# Schematic.net
KiCad netlist of a schematic drawn in Altium Designer
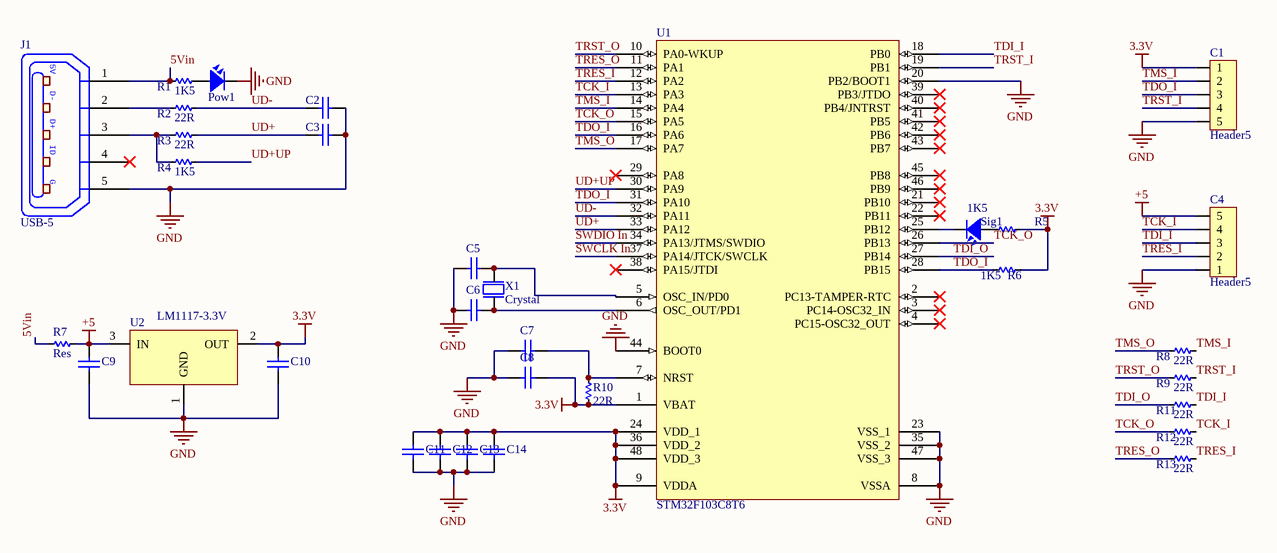
[diagram p0: Schematic.SchDoc]

(export (version "E")
  (design (tool "Eeschema 10.0.6"))
  (components
    (comp (ref "C1")
      (value "Header5")
      (footprint "Header5 SMD")
      (description "Header IDC, 5 x 1 Pin Vertical 2.54mm Pitch (Non-Boxed, Male)")
      (fields
        (field (name "MANUFACTURER") "Würth Elektronik eiSos GmbH")
        (field (name "PARTNO") "613002143121")
        (field (name "CREATED BY") "Karrer Zheng")
      )
      (libsource (lib "MQCrexcelV1.0") (part "Header5"))
    )
    (comp (ref "C2")
      (value "Capacitor Ceramic")
      (footprint "C0805")
      (description "Capacitor")
      (fields (field (name "PUBLISHER") "Altium Limited"))
      (libsource (lib "NBBLib 14-03-2012") (part "CapSMD"))
    )
    (comp (ref "C3")
      (value "Capacitor Ceramic")
      (footprint "C0805")
      (description "Capacitor")
      (fields (field (name "PUBLISHER") "Altium Limited"))
      (libsource (lib "NBBLib 14-03-2012") (part "CapSMD"))
    )
    (comp (ref "C4")
      (value "Header5")
      (footprint "Header5 SMD")
      (description "Header IDC, 5 x 1 Pin Vertical 2.54mm Pitch (Non-Boxed, Male)")
      (fields
        (field (name "MANUFACTURER") "Würth Elektronik eiSos GmbH")
        (field (name "PARTNO") "613002143121")
        (field (name "CREATED BY") "Karrer Zheng")
      )
      (libsource (lib "") (part "Header5_1"))
    )
    (comp (ref "C5")
      (value "Capacitor Ceramic")
      (footprint "C0805")
      (description "Capacitor")
      (fields (field (name "PUBLISHER") "Altium Limited"))
      (libsource (lib "NBBLib 14-03-2012") (part "CapSMD"))
    )
    (comp (ref "C6")
      (value "Capacitor Ceramic")
      (footprint "C0805")
      (description "Capacitor")
      (fields (field (name "PUBLISHER") "Altium Limited"))
      (libsource (lib "NBBLib 14-03-2012") (part "CapSMD"))
    )
    (comp (ref "C7")
      (value "Capacitor Ceramic")
      (footprint "C0805")
      (description "Capacitor")
      (fields (field (name "PUBLISHER") "Altium Limited"))
      (libsource (lib "NBBLib 14-03-2012") (part "CapSMD"))
    )
    (comp (ref "C8")
      (value "Capacitor Ceramic")
      (footprint "C0805")
      (description "Capacitor")
      (fields (field (name "PUBLISHER") "Altium Limited"))
      (libsource (lib "NBBLib 14-03-2012") (part "CapSMD"))
    )
    (comp (ref "C9")
      (value "Capacitor Ceramic")
      (footprint "C0805")
      (description "Capacitor")
      (fields (field (name "PUBLISHER") "Altium Limited"))
      (libsource (lib "NBBLib 14-03-2012") (part "CapSMD"))
    )
    (comp (ref "C10")
      (value "Capacitor Ceramic")
      (footprint "C0805")
      (description "Capacitor")
      (fields (field (name "PUBLISHER") "Altium Limited"))
      (libsource (lib "NBBLib 14-03-2012") (part "CapSMD"))
    )
    (comp (ref "C11")
      (value "Capacitor Ceramic")
      (footprint "C0805")
      (description "Capacitor")
      (fields (field (name "PUBLISHER") "Altium Limited"))
      (libsource (lib "NBBLib 14-03-2012") (part "CapSMD"))
    )
    (comp (ref "C12")
      (value "Capacitor Ceramic")
      (footprint "C0805")
      (description "Capacitor")
      (fields (field (name "PUBLISHER") "Altium Limited"))
      (libsource (lib "NBBLib 14-03-2012") (part "CapSMD"))
    )
    (comp (ref "C13")
      (value "Capacitor Ceramic")
      (footprint "C0805")
      (description "Capacitor")
      (fields (field (name "PUBLISHER") "Altium Limited"))
      (libsource (lib "NBBLib 14-03-2012") (part "CapSMD"))
    )
    (comp (ref "C14")
      (value "Capacitor Ceramic")
      (footprint "C0805")
      (description "Capacitor")
      (fields (field (name "PUBLISHER") "Altium Limited"))
      (libsource (lib "NBBLib 14-03-2012") (part "CapSMD"))
    )
    (comp (ref "J1")
      (value "USB-5")
      (footprint "USB-M1")
      (fields
        (field (name "MANUFACTURER") "FCI")
        (field (name "MANUFACTURER PART NUMBER") "10118193-0001LF")
        (field (name ".CREATOR") "MM")
        (field (name ".CHECKED PCB") "RF")
        (field (name ".CHECKED SCH") "MM")
      )
      (libsource (lib "MQCrexcelV1.0") (part "USB-5"))
    )
    (comp (ref "Pow1")
      (value "LED")
      (footprint "LED-0805-Red")
      (libsource (lib "MQCrexcelV1.0") (part "LED SMD"))
    )
    (comp (ref "R1")
      (value "1K5")
      (footprint "RES-SMD-0603")
      (description "Resistor")
      (fields
        (field (name "MANUFACTURER") "Generic Components")
        (field (name "PUBLISHER") "Altium Hobart Technology Centre")
      )
      (libsource (lib "MQCrexcelV1.0") (part "Res-SMD"))
    )
    (comp (ref "R2")
      (value "22R")
      (footprint "RES-SMD-0603")
      (description "Resistor")
      (fields
        (field (name "MANUFACTURER") "Generic Components")
        (field (name "PUBLISHER") "Altium Hobart Technology Centre")
      )
      (libsource (lib "MQCrexcelV1.0") (part "Res-SMD"))
    )
    (comp (ref "R3")
      (value "22R")
      (footprint "RES-SMD-0603")
      (description "Resistor")
      (fields
        (field (name "MANUFACTURER") "Generic Components")
        (field (name "PUBLISHER") "Altium Hobart Technology Centre")
      )
      (libsource (lib "MQCrexcelV1.0") (part "Res-SMD"))
    )
    (comp (ref "R4")
      (value "1K5")
      (footprint "RES-SMD-0603")
      (description "Resistor")
      (fields
        (field (name "MANUFACTURER") "Generic Components")
        (field (name "PUBLISHER") "Altium Hobart Technology Centre")
      )
      (libsource (lib "MQCrexcelV1.0") (part "Res-SMD"))
    )
    (comp (ref "R5")
      (value "1K5")
      (footprint "RES-SMD-0603")
      (description "Resistor")
      (fields
        (field (name "MANUFACTURER") "Generic Components")
        (field (name "PUBLISHER") "Altium Hobart Technology Centre")
      )
      (libsource (lib "MQCrexcelV1.0") (part "Res-SMD"))
    )
    (comp (ref "R6")
      (value "1K5")
      (footprint "RES-SMD-0603")
      (description "Resistor")
      (fields
        (field (name "MANUFACTURER") "Generic Components")
        (field (name "PUBLISHER") "Altium Hobart Technology Centre")
      )
      (libsource (lib "MQCrexcelV1.0") (part "Res-SMD"))
    )
    (comp (ref "R7")
      (value "Res")
      (footprint "RES-SMD-1206")
      (description "Resistor")
      (fields
        (field (name "MANUFACTURER") "Generic Components")
        (field (name "PUBLISHER") "Altium Hobart Technology Centre")
      )
      (libsource (lib "MQCrexcelV1.0") (part "Res-SMD"))
    )
    (comp (ref "R8")
      (value "22R")
      (footprint "RES-SMD-0603")
      (description "Resistor")
      (fields
        (field (name "MANUFACTURER") "Generic Components")
        (field (name "PUBLISHER") "Altium Hobart Technology Centre")
      )
      (libsource (lib "MQCrexcelV1.0") (part "Res-SMD"))
    )
    (comp (ref "R9")
      (value "22R")
      (footprint "RES-SMD-0603")
      (description "Resistor")
      (fields
        (field (name "MANUFACTURER") "Generic Components")
        (field (name "PUBLISHER") "Altium Hobart Technology Centre")
      )
      (libsource (lib "MQCrexcelV1.0") (part "Res-SMD"))
    )
    (comp (ref "R10")
      (value "22R")
      (footprint "RES-SMD-0603")
      (description "Resistor")
      (fields
        (field (name "MANUFACTURER") "Generic Components")
        (field (name "PUBLISHER") "Altium Hobart Technology Centre")
      )
      (libsource (lib "MQCrexcelV1.0") (part "Res-SMD"))
    )
    (comp (ref "R11")
      (value "22R")
      (footprint "RES-SMD-0603")
      (description "Resistor")
      (fields
        (field (name "MANUFACTURER") "Generic Components")
        (field (name "PUBLISHER") "Altium Hobart Technology Centre")
      )
      (libsource (lib "MQCrexcelV1.0") (part "Res-SMD"))
    )
    (comp (ref "R12")
      (value "22R")
      (footprint "RES-SMD-0603")
      (description "Resistor")
      (fields
        (field (name "MANUFACTURER") "Generic Components")
        (field (name "PUBLISHER") "Altium Hobart Technology Centre")
      )
      (libsource (lib "MQCrexcelV1.0") (part "Res-SMD"))
    )
    (comp (ref "R13")
      (value "22R")
      (footprint "RES-SMD-0603")
      (description "Resistor")
      (fields
        (field (name "MANUFACTURER") "Generic Components")
        (field (name "PUBLISHER") "Altium Hobart Technology Centre")
      )
      (libsource (lib "MQCrexcelV1.0") (part "Res-SMD"))
    )
    (comp (ref "Sig1")
      (value "LED")
      (footprint "LED-0805-Red")
      (libsource (lib "MQCrexcelV1.0") (part "LED SMD"))
    )
    (comp (ref "U1")
      (value "STM32F103C8T6")
      (footprint "LQFP48_N")
      (description "STM32 ARM-based 32-bit MCU with 64 Kbytes Flash, 48-pin LQFP, Industrial Temperature")
      (fields (field (name "PUBLISHER") "Altium Limited"))
      (libsource (lib "ST Microcontroller 32-Bit STM32") (part "STM32F103C8T6"))
    )
    (comp (ref "U2")
      (value "LM1117-3.3V")
      (footprint "SOT223")
      (description "800mA Low-Dropout Linear Regulator")
      (fields (field (name "CREATOR") "Nguyen Ba Bien"))
      (libsource (lib "MQCrexcelV1.0") (part "LM1117"))
    )
    (comp (ref "X1")
      (value "Crystal")
      (footprint "Crystal")
      (libsource (lib "MQCrexcelV1.0") (part "Crystal"))
    )
  )
  (nets
    (net (code "1") (name "+5") (class "Default")
      (node (ref "C4") (pin "5") (pinfunction "5_5") (pintype "passive"))
      (node (ref "C9") (pin "1") (pinfunction "1_1") (pintype "passive"))
      (node (ref "R7") (pin "1") (pinfunction "1_1") (pintype "passive"))
      (node (ref "U2") (pin "3") (pinfunction "IN_3") (pintype "passive"))
    )
    (net (code "2") (name "/5Vin") (class "Default")
      (node (ref "J1") (pin "1") (pinfunction "P1_1") (pintype "passive"))
      (node (ref "R1") (pin "2") (pinfunction "2_2") (pintype "passive"))
      (node (ref "R7") (pin "2") (pinfunction "2_2") (pintype "passive"))
    )
    (net (code "3") (name "/SWCLK In") (class "Default")
      (node (ref "U1") (pin "37") (pinfunction "PA14/JTCK/SWCLK_37") (pintype "bidirectional"))
    )
    (net (code "4") (name "/SWDIO In") (class "Default")
      (node (ref "U1") (pin "34") (pinfunction "PA13/JTMS/SWDIO_34") (pintype "bidirectional"))
    )
    (net (code "5") (name "/TCK_I") (class "Default")
      (node (ref "C4") (pin "4") (pinfunction "4_4") (pintype "passive"))
      (node (ref "R12") (pin "1") (pinfunction "1_1") (pintype "passive"))
      (node (ref "U1") (pin "13") (pinfunction "PA3_13") (pintype "bidirectional"))
    )
    (net (code "6") (name "/TCK_O") (class "Default")
      (node (ref "R12") (pin "2") (pinfunction "2_2") (pintype "passive"))
      (node (ref "U1") (pin "15") (pinfunction "PA5_15") (pintype "bidirectional"))
      (node (ref "U1") (pin "26") (pinfunction "PB13_26") (pintype "bidirectional"))
    )
    (net (code "7") (name "/TDI_I") (class "Default")
      (node (ref "C4") (pin "3") (pinfunction "3_3") (pintype "passive"))
      (node (ref "R11") (pin "1") (pinfunction "1_1") (pintype "passive"))
      (node (ref "U1") (pin "18") (pinfunction "PB0_18") (pintype "bidirectional"))
    )
    (net (code "8") (name "/TDI_O") (class "Default")
      (node (ref "R11") (pin "2") (pinfunction "2_2") (pintype "passive"))
      (node (ref "U1") (pin "27") (pinfunction "PB14_27") (pintype "bidirectional"))
    )
    (net (code "9") (name "/TDO_I") (class "Default")
      (node (ref "C1") (pin "3") (pinfunction "3_3") (pintype "passive"))
      (node (ref "R6") (pin "1") (pinfunction "1_1") (pintype "passive"))
      (node (ref "U1") (pin "16") (pinfunction "PA6_16") (pintype "bidirectional"))
      (node (ref "U1") (pin "28") (pinfunction "PB15_28") (pintype "bidirectional"))
      (node (ref "U1") (pin "31") (pinfunction "PA10_31") (pintype "bidirectional"))
    )
    (net (code "10") (name "/TMS_I") (class "Default")
      (node (ref "C1") (pin "2") (pinfunction "2_2") (pintype "passive"))
      (node (ref "R8") (pin "1") (pinfunction "1_1") (pintype "passive"))
      (node (ref "U1") (pin "14") (pinfunction "PA4_14") (pintype "bidirectional"))
    )
    (net (code "11") (name "/TMS_O") (class "Default")
      (node (ref "R8") (pin "2") (pinfunction "2_2") (pintype "passive"))
      (node (ref "U1") (pin "17") (pinfunction "PA7_17") (pintype "bidirectional"))
    )
    (net (code "12") (name "/TRES_I") (class "Default")
      (node (ref "C4") (pin "2") (pinfunction "2_2") (pintype "passive"))
      (node (ref "R13") (pin "1") (pinfunction "1_1") (pintype "passive"))
      (node (ref "U1") (pin "12") (pinfunction "PA2_12") (pintype "bidirectional"))
    )
    (net (code "13") (name "/TRES_O") (class "Default")
      (node (ref "R13") (pin "2") (pinfunction "2_2") (pintype "passive"))
      (node (ref "U1") (pin "11") (pinfunction "PA1_11") (pintype "bidirectional"))
    )
    (net (code "14") (name "/TRST_I") (class "Default")
      (node (ref "C1") (pin "4") (pinfunction "4_4") (pintype "passive"))
      (node (ref "R9") (pin "1") (pinfunction "1_1") (pintype "passive"))
      (node (ref "U1") (pin "19") (pinfunction "PB1_19") (pintype "bidirectional"))
    )
    (net (code "15") (name "/TRST_O") (class "Default")
      (node (ref "R9") (pin "2") (pinfunction "2_2") (pintype "passive"))
      (node (ref "U1") (pin "10") (pinfunction "PA0-WKUP_10") (pintype "bidirectional"))
    )
    (net (code "16") (name "/UD+") (class "Default")
      (node (ref "C3") (pin "2") (pinfunction "2_2") (pintype "passive"))
      (node (ref "R3") (pin "1") (pinfunction "1_1") (pintype "passive"))
      (node (ref "U1") (pin "33") (pinfunction "PA12_33") (pintype "bidirectional"))
    )
    (net (code "17") (name "/UD+UP") (class "Default")
      (node (ref "R4") (pin "1") (pinfunction "1_1") (pintype "passive"))
      (node (ref "U1") (pin "30") (pinfunction "PA9_30") (pintype "bidirectional"))
    )
    (net (code "18") (name "/UD-") (class "Default")
      (node (ref "C2") (pin "2") (pinfunction "2_2") (pintype "passive"))
      (node (ref "R2") (pin "1") (pinfunction "1_1") (pintype "passive"))
      (node (ref "U1") (pin "32") (pinfunction "PA11_32") (pintype "bidirectional"))
    )
    (net (code "19") (name "3.3V") (class "Default")
      (node (ref "C1") (pin "1") (pinfunction "1_1") (pintype "passive"))
      (node (ref "C10") (pin "1") (pinfunction "1_1") (pintype "passive"))
      (node (ref "C11") (pin "1") (pinfunction "1_1") (pintype "passive"))
      (node (ref "C12") (pin "1") (pinfunction "1_1") (pintype "passive"))
      (node (ref "C13") (pin "1") (pinfunction "1_1") (pintype "passive"))
      (node (ref "C14") (pin "1") (pinfunction "1_1") (pintype "passive"))
      (node (ref "C8") (pin "2") (pinfunction "2_2") (pintype "passive"))
      (node (ref "R10") (pin "2") (pinfunction "2_2") (pintype "passive"))
      (node (ref "R5") (pin "2") (pinfunction "2_2") (pintype "passive"))
      (node (ref "R6") (pin "2") (pinfunction "2_2") (pintype "passive"))
      (node (ref "U1") (pin "1") (pinfunction "VBAT_1") (pintype "power_in"))
      (node (ref "U1") (pin "24") (pinfunction "VDD_1_24") (pintype "power_in"))
      (node (ref "U1") (pin "36") (pinfunction "VDD_2_36") (pintype "power_in"))
      (node (ref "U1") (pin "48") (pinfunction "VDD_3_48") (pintype "power_in"))
      (node (ref "U1") (pin "9") (pinfunction "VDDA_9") (pintype "power_in"))
      (node (ref "U2") (pin "2") (pinfunction "OUT_2") (pintype "passive"))
    )
    (net (code "20") (name "GND") (class "Default")
      (node (ref "C1") (pin "5") (pinfunction "5_5") (pintype "passive"))
      (node (ref "C10") (pin "2") (pinfunction "2_2") (pintype "passive"))
      (node (ref "C11") (pin "2") (pinfunction "2_2") (pintype "passive"))
      (node (ref "C12") (pin "2") (pinfunction "2_2") (pintype "passive"))
      (node (ref "C13") (pin "2") (pinfunction "2_2") (pintype "passive"))
      (node (ref "C14") (pin "2") (pinfunction "2_2") (pintype "passive"))
      (node (ref "C2") (pin "1") (pinfunction "1_1") (pintype "passive"))
      (node (ref "C3") (pin "1") (pinfunction "1_1") (pintype "passive"))
      (node (ref "C4") (pin "1") (pinfunction "1_1") (pintype "passive"))
      (node (ref "C5") (pin "1") (pinfunction "1_1") (pintype "passive"))
      (node (ref "C6") (pin "1") (pinfunction "1_1") (pintype "passive"))
      (node (ref "C7") (pin "1") (pinfunction "1_1") (pintype "passive"))
      (node (ref "C8") (pin "1") (pinfunction "1_1") (pintype "passive"))
      (node (ref "C9") (pin "2") (pinfunction "2_2") (pintype "passive"))
      (node (ref "J1") (pin "5") (pinfunction "P5_5") (pintype "passive"))
      (node (ref "Pow1") (pin "2") (pinfunction "2_2") (pintype "passive"))
      (node (ref "U1") (pin "20") (pinfunction "PB2/BOOT1_20") (pintype "bidirectional"))
      (node (ref "U1") (pin "23") (pinfunction "VSS_1_23") (pintype "power_in"))
      (node (ref "U1") (pin "35") (pinfunction "VSS_2_35") (pintype "power_in"))
      (node (ref "U1") (pin "44") (pinfunction "BOOT0_44") (pintype "input"))
      (node (ref "U1") (pin "47") (pinfunction "VSS_3_47") (pintype "power_in"))
      (node (ref "U1") (pin "8") (pinfunction "VSSA_8") (pintype "power_in"))
      (node (ref "U2") (pin "1") (pinfunction "GND_1") (pintype "passive"))
    )
    (net (code "21") (name "Net-(J1-P2)") (class "Default")
      (node (ref "J1") (pin "2") (pinfunction "P2_2") (pintype "passive"))
      (node (ref "R2") (pin "2") (pinfunction "2_2") (pintype "passive"))
    )
    (net (code "22") (name "Net-(J1-P3)") (class "Default")
      (node (ref "J1") (pin "3") (pinfunction "P3_3") (pintype "passive"))
      (node (ref "R3") (pin "2") (pinfunction "2_2") (pintype "passive"))
      (node (ref "R4") (pin "2") (pinfunction "2_2") (pintype "passive"))
    )
    (net (code "23") (name "Net-(Pow1-Pad1)") (class "Default")
      (node (ref "Pow1") (pin "1") (pinfunction "1_1") (pintype "passive"))
      (node (ref "R1") (pin "1") (pinfunction "1_1") (pintype "passive"))
    )
    (net (code "24") (name "Net-(R5-Pad1)") (class "Default")
      (node (ref "R5") (pin "1") (pinfunction "1_1") (pintype "passive"))
      (node (ref "Sig1") (pin "1") (pinfunction "1_1") (pintype "passive"))
    )
    (net (code "25") (name "Net-(U1-NRST)") (class "Default")
      (node (ref "C7") (pin "2") (pinfunction "2_2") (pintype "passive"))
      (node (ref "R10") (pin "1") (pinfunction "1_1") (pintype "passive"))
      (node (ref "U1") (pin "7") (pinfunction "NRST_7") (pintype "bidirectional"))
    )
    (net (code "26") (name "Net-(U1-OSC_IN{slash}PD0)") (class "Default")
      (node (ref "C5") (pin "2") (pinfunction "2_2") (pintype "passive"))
      (node (ref "U1") (pin "5") (pinfunction "OSC_IN/PD0_5") (pintype "input"))
      (node (ref "X1") (pin "2") (pinfunction "2_2") (pintype "passive"))
    )
    (net (code "27") (name "Net-(U1-OSC_OUT{slash}PD1)") (class "Default")
      (node (ref "C6") (pin "2") (pinfunction "2_2") (pintype "passive"))
      (node (ref "U1") (pin "6") (pinfunction "OSC_OUT/PD1_6") (pintype "output"))
      (node (ref "X1") (pin "1") (pinfunction "1_1") (pintype "passive"))
    )
    (net (code "28") (name "Net-(U1-PB12)") (class "Default")
      (node (ref "Sig1") (pin "2") (pinfunction "2_2") (pintype "passive"))
      (node (ref "U1") (pin "25") (pinfunction "PB12_25") (pintype "bidirectional"))
    )
    (net (code "29") (name "unconnected-(J1-P4-Pad4)") (class "Default")
      (node (ref "J1") (pin "4") (pinfunction "P4_4") (pintype "passive+no_connect"))
    )
    (net (code "30") (name "unconnected-(U1-PA8-Pad29)") (class "Default")
      (node (ref "U1") (pin "29") (pinfunction "PA8_29") (pintype "bidirectional+no_connect"))
    )
    (net (code "31") (name "unconnected-(U1-PA15{slash}JTDI-Pad38)") (class "Default")
      (node (ref "U1") (pin "38") (pinfunction "PA15/JTDI_38") (pintype "bidirectional+no_connect"))
    )
    (net (code "32") (name "unconnected-(U1-PB3{slash}JTDO-Pad39)") (class "Default")
      (node (ref "U1") (pin "39") (pinfunction "PB3/JTDO_39") (pintype "bidirectional+no_connect"))
    )
    (net (code "33") (name "unconnected-(U1-PB4{slash}JNTRST-Pad40)") (class "Default")
      (node (ref "U1") (pin "40") (pinfunction "PB4/JNTRST_40") (pintype "bidirectional+no_connect"))
    )
    (net (code "34") (name "unconnected-(U1-PB5-Pad41)") (class "Default")
      (node (ref "U1") (pin "41") (pinfunction "PB5_41") (pintype "bidirectional+no_connect"))
    )
    (net (code "35") (name "unconnected-(U1-PB6-Pad42)") (class "Default")
      (node (ref "U1") (pin "42") (pinfunction "PB6_42") (pintype "bidirectional+no_connect"))
    )
    (net (code "36") (name "unconnected-(U1-PB7-Pad43)") (class "Default")
      (node (ref "U1") (pin "43") (pinfunction "PB7_43") (pintype "bidirectional+no_connect"))
    )
    (net (code "37") (name "unconnected-(U1-PB8-Pad45)") (class "Default")
      (node (ref "U1") (pin "45") (pinfunction "PB8_45") (pintype "bidirectional+no_connect"))
    )
    (net (code "38") (name "unconnected-(U1-PB9-Pad46)") (class "Default")
      (node (ref "U1") (pin "46") (pinfunction "PB9_46") (pintype "bidirectional+no_connect"))
    )
    (net (code "39") (name "unconnected-(U1-PB10-Pad21)") (class "Default")
      (node (ref "U1") (pin "21") (pinfunction "PB10_21") (pintype "bidirectional+no_connect"))
    )
    (net (code "40") (name "unconnected-(U1-PB11-Pad22)") (class "Default")
      (node (ref "U1") (pin "22") (pinfunction "PB11_22") (pintype "bidirectional+no_connect"))
    )
    (net (code "41") (name "unconnected-(U1-PC13-TAMPER-RTC-Pad2)") (class "Default")
      (node (ref "U1") (pin "2") (pinfunction "PC13-TAMPER-RTC_2") (pintype "bidirectional+no_connect"))
    )
    (net (code "42") (name "unconnected-(U1-PC14-OSC32_IN-Pad3)") (class "Default")
      (node (ref "U1") (pin "3") (pinfunction "PC14-OSC32_IN_3") (pintype "bidirectional+no_connect"))
    )
    (net (code "43") (name "unconnected-(U1-PC15-OSC32_OUT-Pad4)") (class "Default")
      (node (ref "U1") (pin "4") (pinfunction "PC15-OSC32_OUT_4") (pintype "bidirectional+no_connect"))
    )
  )
)
